# MainBoard.net
KiCad netlist of a schematic drawn in Altium Designer
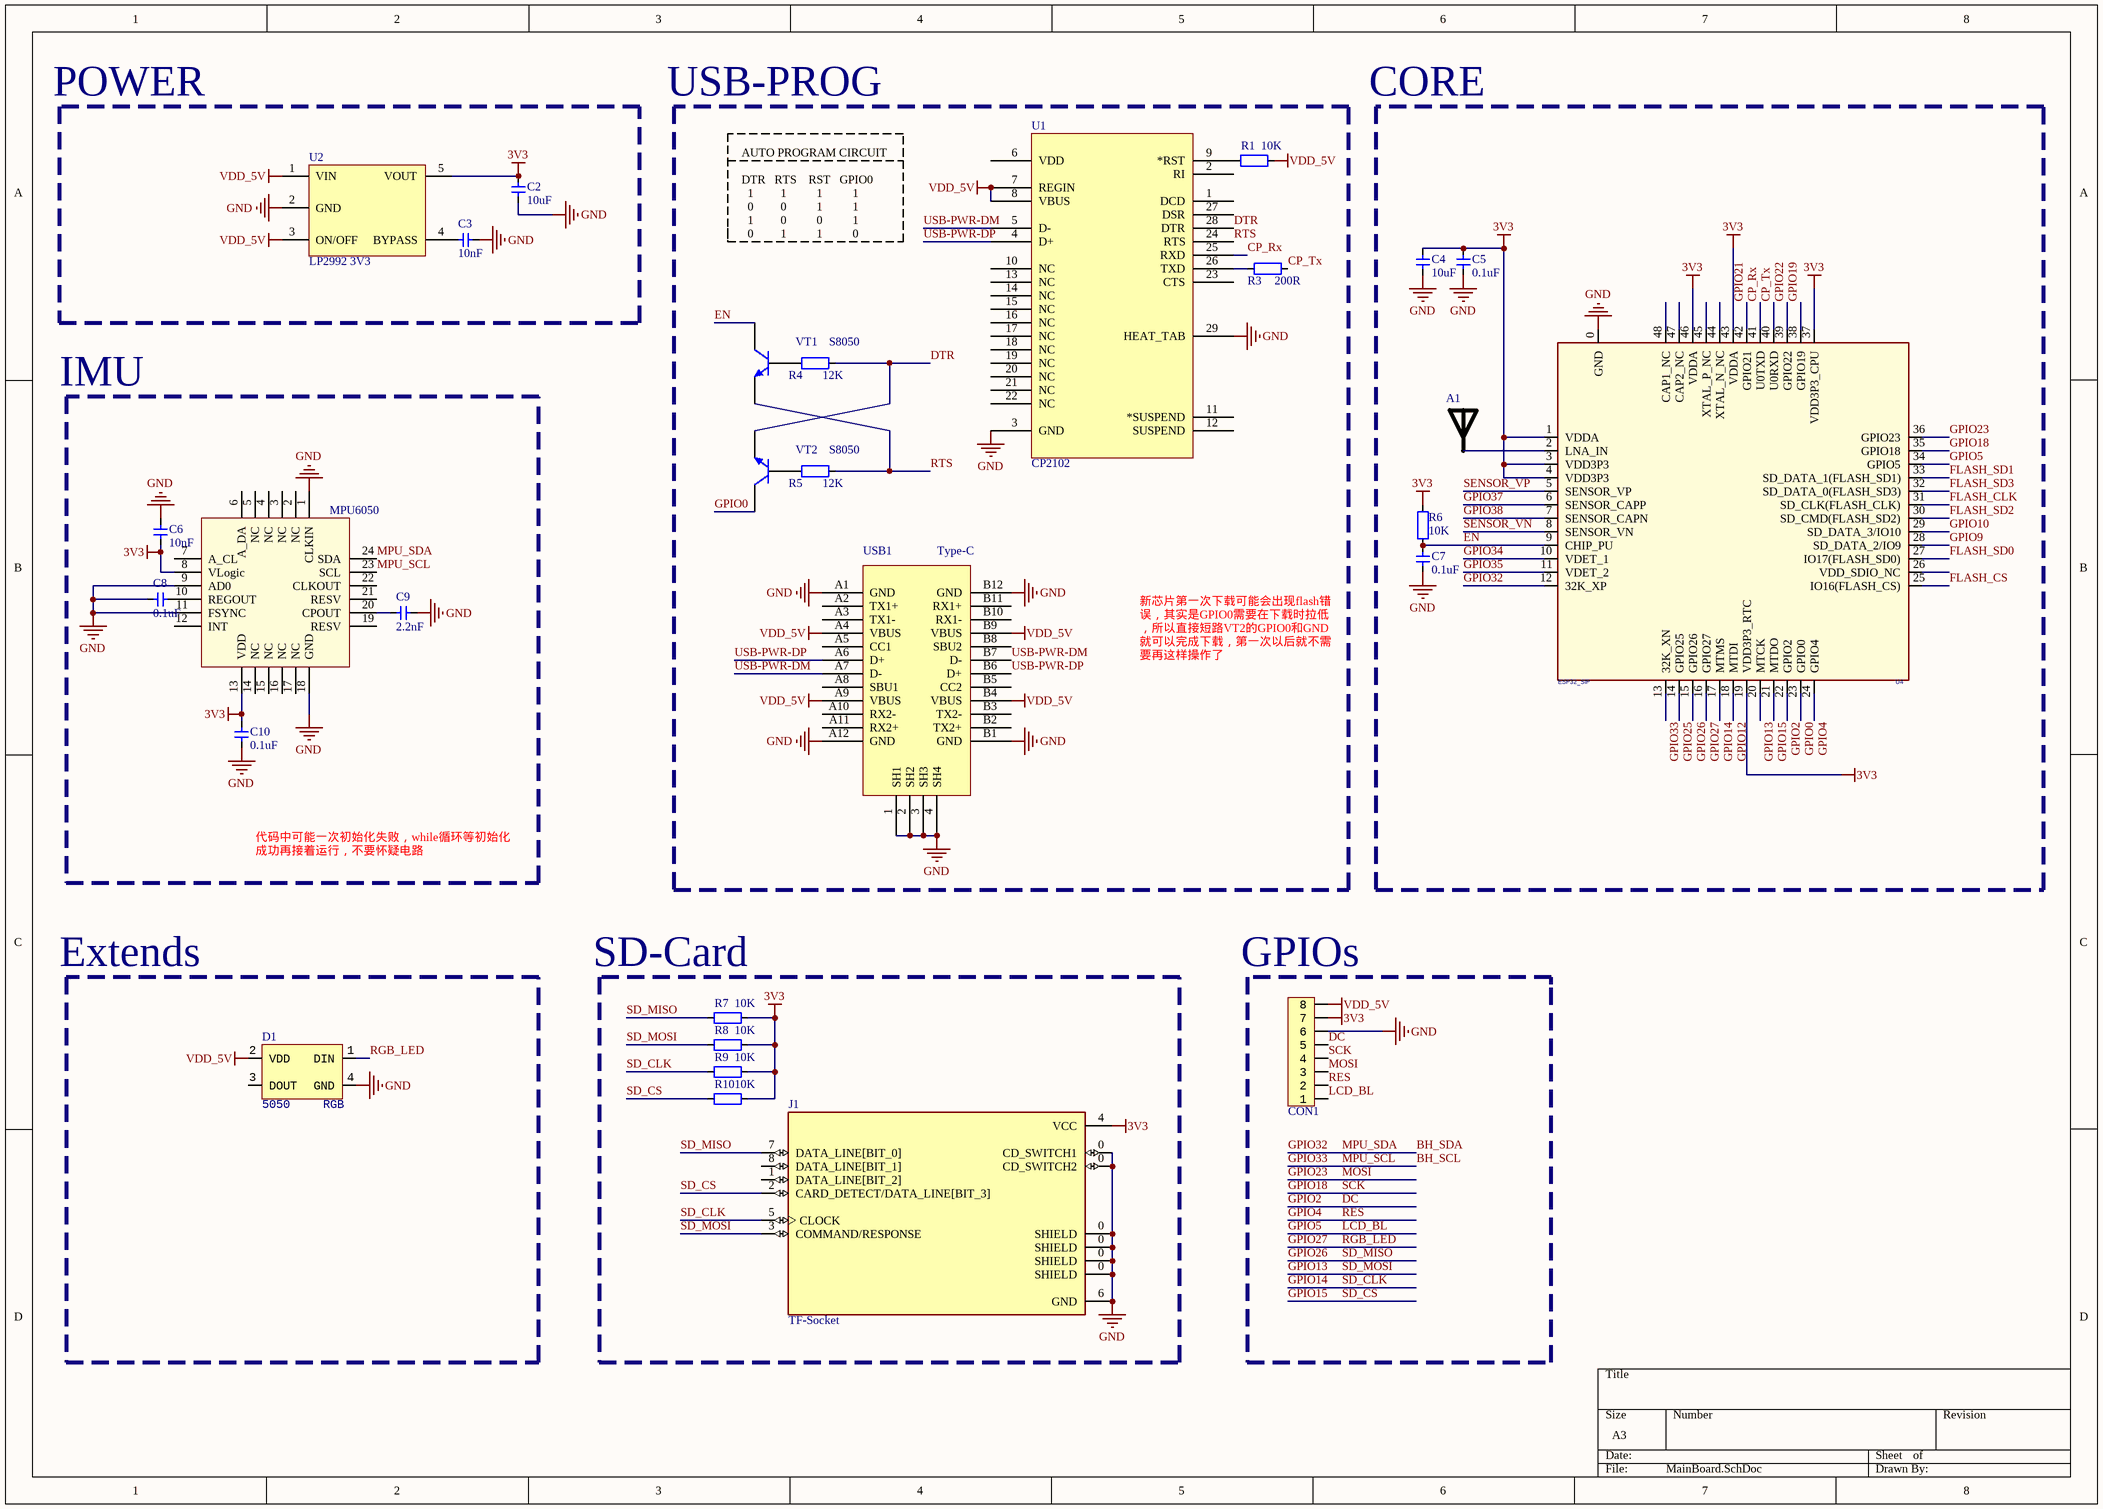
[diagram p0: MainBoard.SchDoc]

(export (version "E")
  (design (tool "Eeschema 10.0.6"))
  (components
    (comp (ref "A1")
      (value "RAINSUN")
      (footprint "ANT-Rainsun-AN5120")
      (libsource (lib "MyPcbLib") (part "ANT-Rainsun-AP5120"))
    )
    (comp (ref "C2")
      (value "10uF")
      (footprint "CAP_0402")
      (description "Capacitor")
      (libsource (lib "MyPcbLib") (part "电容-0402"))
    )
    (comp (ref "C3")
      (value "10nF")
      (footprint "CAP_0402")
      (description "Capacitor")
      (libsource (lib "MyPcbLib") (part "电容-0402"))
    )
    (comp (ref "C4")
      (value "10uF")
      (footprint "CAP_0402")
      (description "Capacitor")
      (libsource (lib "MyPcbLib") (part "电容-0402"))
    )
    (comp (ref "C5")
      (value "0.1uF")
      (footprint "CAP_0402")
      (description "Capacitor")
      (libsource (lib "MyPcbLib") (part "电容-0402"))
    )
    (comp (ref "C6")
      (value "10nF")
      (footprint "CAP_0402")
      (description "Capacitor")
      (libsource (lib "MyPcbLib") (part "电容-0402"))
    )
    (comp (ref "C7")
      (value "0.1uF")
      (footprint "CAP_0402")
      (description "Capacitor")
      (libsource (lib "MyPcbLib") (part "电容-0402"))
    )
    (comp (ref "C8")
      (value "0.1uF")
      (footprint "CAP_0402")
      (description "Capacitor")
      (libsource (lib "MyPcbLib") (part "电容-0402"))
    )
    (comp (ref "C9")
      (value "2.2nF")
      (footprint "CAP_0402")
      (description "Capacitor")
      (libsource (lib "MyPcbLib") (part "电容-0402"))
    )
    (comp (ref "C10")
      (value "0.1uF")
      (footprint "CAP_0402")
      (description "Capacitor")
      (libsource (lib "MyPcbLib") (part "电容-0402"))
    )
    (comp (ref "CON1")
      (value "FFC_0.5_8")
      (footprint "FFC_0.5_8")
      (description "FFC")
      (libsource (lib "KitSprout") (part "FFC_0.5_8"))
    )
    (comp (ref "D1")
      (value "RGB")
      (footprint "LED_WS2812_CE")
      (description "LED")
      (fields (field (name "TYPE") "5050"))
      (libsource (lib "KitSprout") (part "LED_5050_WS2812B"))
    )
    (comp (ref "J1")
      (value "TF-Socket")
      (footprint "TF_F")
      (description "10 _8 + 2_ Position Card Connector Secure Digital - microSDâ„¢ Surface Mount, Right Angle Gold")
      (fields (field (name "MP") "1140084168") (field (name "MF") "Amphenol Commercial Products"))
      (libsource (lib "MyPcbLib") (part "TF-Socket"))
    )
    (comp (ref "R1")
      (value "10K")
      (footprint "RES_0402")
      (description "Resistor")
      (libsource (lib "") (part "电阻-0402_1"))
    )
    (comp (ref "R3")
      (value "200R")
      (footprint "RES_0402")
      (description "Resistor")
      (libsource (lib "") (part "电阻-0402_1"))
    )
    (comp (ref "R4")
      (value "12K")
      (footprint "RES_0402")
      (description "Resistor")
      (libsource (lib "") (part "电阻-0402_1"))
    )
    (comp (ref "R5")
      (value "12K")
      (footprint "RES_0402")
      (description "Resistor")
      (libsource (lib "") (part "电阻-0402_1"))
    )
    (comp (ref "R6")
      (value "10K")
      (footprint "RES_0402")
      (description "Resistor")
      (libsource (lib "MyPcbLib") (part "电阻-0402"))
    )
    (comp (ref "R7")
      (value "10K")
      (footprint "RES_0402")
      (description "Resistor")
      (libsource (lib "") (part "电阻-0402_1"))
    )
    (comp (ref "R8")
      (value "10K")
      (footprint "RES_0402")
      (description "Resistor")
      (libsource (lib "") (part "电阻-0402_1"))
    )
    (comp (ref "R9")
      (value "10K")
      (footprint "RES_0402")
      (description "Resistor")
      (libsource (lib "") (part "电阻-0402_1"))
    )
    (comp (ref "R10")
      (value "10K")
      (footprint "RES_0402")
      (description "Resistor")
      (libsource (lib "") (part "电阻-0402_1"))
    )
    (comp (ref "U1")
      (value "CP2102")
      (footprint "QFN-28")
      (description "USB转TTL")
      (libsource (lib "mLib") (part "CP2102"))
    )
    (comp (ref "U2")
      (value "LP2992 3V3")
      (footprint "SOT23-5")
      (description "LDO")
      (libsource (lib "MyPcbLib") (part "LP2992"))
    )
    (comp (ref "U3")
      (value "MPU6050")
      (footprint "QFN-24")
      (description "六轴传感器")
      (libsource (lib "mLib") (part "MPU6050"))
    )
    (comp (ref "U4")
      (value "ESP32_SIP")
      (footprint "QFN-48_7X7")
      (libsource (lib "MyPcbLib") (part "ESP32-PICO"))
    )
    (comp (ref "USB1")
      (value "Type-C")
      (footprint "Type-C-TOP")
      (libsource (lib "MyPcbLib") (part "USB-Type-C-TOP"))
    )
    (comp (ref "VT1")
      (value "S8050")
      (footprint "SMT_TRIODE_NPN")
      (description "Surface mount NPN transistor, package SOT-23")
      (libsource (lib "MyPcbLib") (part "SMT_TRIODE_NPN"))
    )
    (comp (ref "VT2")
      (value "S8050")
      (footprint "SMT_TRIODE_NPN")
      (description "Surface mount NPN transistor, package SOT-23")
      (libsource (lib "MyPcbLib") (part "SMT_TRIODE_NPN"))
    )
  )
  (nets
    (net (code "1") (name "/BH_SCL") (class "Default")
      (node (ref "U3") (pin "23") (pinfunction "SCL_23") (pintype "passive"))
      (node (ref "U4") (pin "13") (pinfunction "32K_XN_13") (pintype "passive"))
    )
    (net (code "2") (name "/BH_SDA") (class "Default")
      (node (ref "U3") (pin "24") (pinfunction "SDA_24") (pintype "passive"))
      (node (ref "U4") (pin "12") (pinfunction "32K_XP_12") (pintype "passive"))
    )
    (net (code "3") (name "/CP_Rx") (class "Default")
      (node (ref "U1") (pin "25") (pinfunction "RXD_25") (pintype "passive"))
      (node (ref "U4") (pin "41") (pinfunction "U0TXD_41") (pintype "power_in"))
    )
    (net (code "4") (name "/CP_Tx") (class "Default")
      (node (ref "R3") (pin "1") (pinfunction "1_1") (pintype "passive"))
      (node (ref "U4") (pin "40") (pinfunction "U0RXD_40") (pintype "power_in"))
    )
    (net (code "5") (name "/DC") (class "Default")
      (node (ref "CON1") (pin "5") (pinfunction "5_5") (pintype "passive"))
      (node (ref "U4") (pin "22") (pinfunction "GPIO2_22") (pintype "passive"))
    )
    (net (code "6") (name "/DTR") (class "Default")
      (node (ref "R4") (pin "1") (pinfunction "1_1") (pintype "passive"))
      (node (ref "U1") (pin "28") (pinfunction "DTR_28") (pintype "passive"))
      (node (ref "VT2") (pin "2") (pinfunction "E_2") (pintype "passive"))
    )
    (net (code "7") (name "/EN") (class "Default")
      (node (ref "C7") (pin "1") (pinfunction "1_1") (pintype "passive"))
      (node (ref "R6") (pin "2") (pinfunction "2_2") (pintype "passive"))
      (node (ref "U4") (pin "9") (pinfunction "CHIP_PU_9") (pintype "passive"))
      (node (ref "VT1") (pin "3") (pinfunction "C_3") (pintype "passive"))
    )
    (net (code "8") (name "/FLASH_CLK") (class "Default")
      (node (ref "U4") (pin "31") (pinfunction "SD_CLK(FLASH_CLK)_31") (pintype "passive"))
    )
    (net (code "9") (name "/FLASH_CS") (class "Default")
      (node (ref "U4") (pin "25") (pinfunction "IO16(FLASH_CS)_25") (pintype "passive"))
    )
    (net (code "10") (name "/FLASH_SD0") (class "Default")
      (node (ref "U4") (pin "27") (pinfunction "IO17(FLASH_SD0)_27") (pintype "passive"))
    )
    (net (code "11") (name "/FLASH_SD1") (class "Default")
      (node (ref "U4") (pin "33") (pinfunction "SD_DATA_1(FLASH_SD1)_33") (pintype "passive"))
    )
    (net (code "12") (name "/FLASH_SD2") (class "Default")
      (node (ref "U4") (pin "30") (pinfunction "SD_CMD(FLASH_SD2)_30") (pintype "passive"))
    )
    (net (code "13") (name "/FLASH_SD3") (class "Default")
      (node (ref "U4") (pin "32") (pinfunction "SD_DATA_0(FLASH_SD3)_32") (pintype "passive"))
    )
    (net (code "14") (name "/GPIO0") (class "Default")
      (node (ref "U4") (pin "23") (pinfunction "GPIO0_23") (pintype "passive"))
      (node (ref "VT2") (pin "3") (pinfunction "C_3") (pintype "passive"))
    )
    (net (code "15") (name "/GPIO4") (class "Default")
      (node (ref "CON1") (pin "2") (pinfunction "2_2") (pintype "passive"))
      (node (ref "U4") (pin "24") (pinfunction "GPIO4_24") (pintype "passive"))
    )
    (net (code "16") (name "/GPIO5") (class "Default")
      (node (ref "CON1") (pin "1") (pinfunction "1_1") (pintype "passive"))
      (node (ref "U4") (pin "34") (pinfunction "GPIO5_34") (pintype "passive"))
    )
    (net (code "17") (name "/GPIO9") (class "Default")
      (node (ref "U4") (pin "28") (pinfunction "SD_DATA_2/IO9_28") (pintype "passive"))
    )
    (net (code "18") (name "/GPIO10") (class "Default")
      (node (ref "U4") (pin "29") (pinfunction "SD_DATA_3/IO10_29") (pintype "passive"))
    )
    (net (code "19") (name "/GPIO12") (class "Default")
      (node (ref "U4") (pin "18") (pinfunction "MTDI_18") (pintype "passive"))
    )
    (net (code "20") (name "/GPIO13") (class "Default")
      (node (ref "J1") (pin "3") (pinfunction "COMMAND/RESPONSE_3") (pintype "bidirectional"))
      (node (ref "R8") (pin "2") (pinfunction "2_2") (pintype "passive"))
      (node (ref "U4") (pin "20") (pinfunction "MTCK_20") (pintype "passive"))
    )
    (net (code "21") (name "/GPIO14") (class "Default")
      (node (ref "J1") (pin "5") (pinfunction "CLOCK_5") (pintype "bidirectional"))
      (node (ref "R9") (pin "2") (pinfunction "2_2") (pintype "passive"))
      (node (ref "U4") (pin "17") (pinfunction "MTMS_17") (pintype "passive"))
    )
    (net (code "22") (name "/GPIO15") (class "Default")
      (node (ref "J1") (pin "2") (pinfunction "CARD_DETECT/DATA_LINE[BIT_3]_2") (pintype "bidirectional"))
      (node (ref "R10") (pin "2") (pinfunction "2_2") (pintype "passive"))
      (node (ref "U4") (pin "21") (pinfunction "MTDO_21") (pintype "passive"))
    )
    (net (code "23") (name "/GPIO18") (class "Default")
      (node (ref "CON1") (pin "4") (pinfunction "4_4") (pintype "passive"))
      (node (ref "U4") (pin "35") (pinfunction "GPIO18_35") (pintype "passive"))
    )
    (net (code "24") (name "/GPIO19") (class "Default")
      (node (ref "U4") (pin "38") (pinfunction "GPIO19_38") (pintype "passive"))
    )
    (net (code "25") (name "/GPIO21") (class "Default")
      (node (ref "U4") (pin "42") (pinfunction "GPIO21_42") (pintype "passive"))
    )
    (net (code "26") (name "/GPIO22") (class "Default")
      (node (ref "U4") (pin "39") (pinfunction "GPIO22_39") (pintype "passive"))
    )
    (net (code "27") (name "/GPIO23") (class "Default")
      (node (ref "CON1") (pin "3") (pinfunction "3_3") (pintype "passive"))
      (node (ref "U4") (pin "36") (pinfunction "GPIO23_36") (pintype "passive"))
    )
    (net (code "28") (name "/GPIO25") (class "Default")
      (node (ref "U4") (pin "14") (pinfunction "GPIO25_14") (pintype "passive"))
    )
    (net (code "29") (name "/GPIO26") (class "Default")
      (node (ref "J1") (pin "7") (pinfunction "DATA_LINE[BIT_0]_7") (pintype "bidirectional"))
      (node (ref "R7") (pin "2") (pinfunction "2_2") (pintype "passive"))
      (node (ref "U4") (pin "15") (pinfunction "GPIO26_15") (pintype "passive"))
    )
    (net (code "30") (name "/GPIO27") (class "Default")
      (node (ref "D1") (pin "1") (pinfunction "DIN_1") (pintype "passive"))
      (node (ref "U4") (pin "16") (pinfunction "GPIO27_16") (pintype "passive"))
    )
    (net (code "31") (name "/GPIO34") (class "Default")
      (node (ref "U4") (pin "10") (pinfunction "VDET_1_10") (pintype "passive"))
    )
    (net (code "32") (name "/GPIO35") (class "Default")
      (node (ref "U4") (pin "11") (pinfunction "VDET_2_11") (pintype "passive"))
    )
    (net (code "33") (name "/GPIO37") (class "Default")
      (node (ref "U4") (pin "6") (pinfunction "SENSOR_CAPP_6") (pintype "passive"))
    )
    (net (code "34") (name "/GPIO38") (class "Default")
      (node (ref "U4") (pin "7") (pinfunction "SENSOR_CAPN_7") (pintype "passive"))
    )
    (net (code "35") (name "/RTS") (class "Default")
      (node (ref "R5") (pin "1") (pinfunction "1_1") (pintype "passive"))
      (node (ref "U1") (pin "24") (pinfunction "RTS_24") (pintype "passive"))
      (node (ref "VT1") (pin "2") (pinfunction "E_2") (pintype "passive"))
    )
    (net (code "36") (name "/SENSOR_VN") (class "Default")
      (node (ref "U4") (pin "8") (pinfunction "SENSOR_VN_8") (pintype "passive"))
    )
    (net (code "37") (name "/SENSOR_VP") (class "Default")
      (node (ref "U4") (pin "5") (pinfunction "SENSOR_VP_5") (pintype "passive"))
    )
    (net (code "38") (name "/USB-PWR-DM") (class "Default")
      (node (ref "U1") (pin "5") (pinfunction "D-_5") (pintype "passive"))
      (node (ref "USB1") (pin "A7") (pinfunction "D-_A7") (pintype "passive"))
      (node (ref "USB1") (pin "B7") (pinfunction "D-_B7") (pintype "passive"))
    )
    (net (code "39") (name "/USB-PWR-DP") (class "Default")
      (node (ref "U1") (pin "4") (pinfunction "D+_4") (pintype "passive"))
      (node (ref "USB1") (pin "A6") (pinfunction "D+_A6") (pintype "passive"))
      (node (ref "USB1") (pin "B6") (pinfunction "D+_B6") (pintype "passive"))
    )
    (net (code "40") (name "3V3") (class "Default")
      (node (ref "C10") (pin "2") (pinfunction "2_2") (pintype "passive"))
      (node (ref "C2") (pin "2") (pinfunction "2_2") (pintype "passive"))
      (node (ref "C4") (pin "2") (pinfunction "2_2") (pintype "passive"))
      (node (ref "C5") (pin "2") (pinfunction "2_2") (pintype "passive"))
      (node (ref "C6") (pin "1") (pinfunction "1_1") (pintype "passive"))
      (node (ref "CON1") (pin "7") (pinfunction "7_7") (pintype "passive"))
      (node (ref "J1") (pin "4") (pinfunction "VCC_4") (pintype "power_in"))
      (node (ref "R10") (pin "1") (pinfunction "1_1") (pintype "passive"))
      (node (ref "R6") (pin "1") (pinfunction "1_1") (pintype "passive"))
      (node (ref "R7") (pin "1") (pinfunction "1_1") (pintype "passive"))
      (node (ref "R8") (pin "1") (pinfunction "1_1") (pintype "passive"))
      (node (ref "R9") (pin "1") (pinfunction "1_1") (pintype "passive"))
      (node (ref "U2") (pin "5") (pinfunction "VOUT_5") (pintype "passive"))
      (node (ref "U3") (pin "13") (pinfunction "VDD_13") (pintype "passive"))
      (node (ref "U3") (pin "8") (pinfunction "VLogic_8") (pintype "passive"))
      (node (ref "U4") (pin "1") (pinfunction "VDDA_1") (pintype "power_in"))
      (node (ref "U4") (pin "19") (pinfunction "VDD3P3_RTC_19") (pintype "power_in"))
      (node (ref "U4") (pin "3") (pinfunction "VDD3P3_3") (pintype "power_in"))
      (node (ref "U4") (pin "37") (pinfunction "VDD3P3_CPU_37") (pintype "power_in"))
      (node (ref "U4") (pin "4") (pinfunction "VDD3P3_4") (pintype "power_in"))
      (node (ref "U4") (pin "43") (pinfunction "VDDA_43") (pintype "power_in"))
      (node (ref "U4") (pin "46") (pinfunction "VDDA_46") (pintype "power_in"))
    )
    (net (code "41") (name "GND") (class "Default")
      (node (ref "C10") (pin "1") (pinfunction "1_1") (pintype "passive"))
      (node (ref "C2") (pin "1") (pinfunction "1_1") (pintype "passive"))
      (node (ref "C3") (pin "1") (pinfunction "1_1") (pintype "passive"))
      (node (ref "C4") (pin "1") (pinfunction "1_1") (pintype "passive"))
      (node (ref "C5") (pin "1") (pinfunction "1_1") (pintype "passive"))
      (node (ref "C6") (pin "2") (pinfunction "2_2") (pintype "passive"))
      (node (ref "C7") (pin "2") (pinfunction "2_2") (pintype "passive"))
      (node (ref "C8") (pin "2") (pinfunction "2_2") (pintype "passive"))
      (node (ref "C9") (pin "1") (pinfunction "1_1") (pintype "passive"))
      (node (ref "CON1") (pin "6") (pinfunction "6_6") (pintype "passive"))
      (node (ref "D1") (pin "4") (pinfunction "GND_4") (pintype "passive"))
      (node (ref "J1") (pin "0") (pinfunction "SHIELD_0") (pintype "passive"))
      (node (ref "J1") (pin "6") (pinfunction "GND_6") (pintype "power_in"))
      (node (ref "U1") (pin "29") (pinfunction "HEAT_TAB_29") (pintype "passive"))
      (node (ref "U1") (pin "3") (pinfunction "GND_3") (pintype "passive"))
      (node (ref "U2") (pin "2") (pinfunction "GND_2") (pintype "passive"))
      (node (ref "U3") (pin "1") (pinfunction "CLKIN_1") (pintype "passive"))
      (node (ref "U3") (pin "11") (pinfunction "FSYNC_11") (pintype "passive"))
      (node (ref "U3") (pin "18") (pinfunction "GND_18") (pintype "passive"))
      (node (ref "U3") (pin "9") (pinfunction "AD0_9") (pintype "passive"))
      (node (ref "U4") (pin "0") (pinfunction "GND_0") (pintype "power_in"))
      (node (ref "USB1") (pin "1") (pinfunction "SH1_1") (pintype "passive"))
      (node (ref "USB1") (pin "2") (pinfunction "SH2_2") (pintype "passive"))
      (node (ref "USB1") (pin "3") (pinfunction "SH3_3") (pintype "passive"))
      (node (ref "USB1") (pin "4") (pinfunction "SH4_4") (pintype "passive"))
      (node (ref "USB1") (pin "A1") (pinfunction "GND_A1") (pintype "passive"))
      (node (ref "USB1") (pin "A12") (pinfunction "GND_A12") (pintype "passive"))
      (node (ref "USB1") (pin "B1") (pinfunction "GND_B1") (pintype "passive"))
      (node (ref "USB1") (pin "B12") (pinfunction "GND_B12") (pintype "passive"))
    )
    (net (code "42") (name "Net-(U1-*RST)") (class "Default")
      (node (ref "R1") (pin "2") (pinfunction "2_2") (pintype "passive"))
      (node (ref "U1") (pin "9") (pinfunction "*RST_9") (pintype "passive"))
    )
    (net (code "43") (name "Net-(U1-TXD)") (class "Default")
      (node (ref "R3") (pin "2") (pinfunction "2_2") (pintype "passive"))
      (node (ref "U1") (pin "26") (pinfunction "TXD_26") (pintype "passive"))
    )
    (net (code "44") (name "Net-(U2-BYPASS)") (class "Default")
      (node (ref "C3") (pin "2") (pinfunction "2_2") (pintype "passive"))
      (node (ref "U2") (pin "4") (pinfunction "BYPASS_4") (pintype "passive"))
    )
    (net (code "45") (name "Net-(U3-CPOUT)") (class "Default")
      (node (ref "C9") (pin "2") (pinfunction "2_2") (pintype "passive"))
      (node (ref "U3") (pin "20") (pinfunction "CPOUT_20") (pintype "passive"))
    )
    (net (code "46") (name "Net-(U3-REGOUT)") (class "Default")
      (node (ref "C8") (pin "1") (pinfunction "1_1") (pintype "passive"))
      (node (ref "U3") (pin "10") (pinfunction "REGOUT_10") (pintype "passive"))
    )
    (net (code "47") (name "Net-(U4-LNA_IN)") (class "Default")
      (node (ref "A1") (pin "1") (pinfunction "1_1") (pintype "passive"))
      (node (ref "U4") (pin "2") (pinfunction "LNA_IN_2") (pintype "passive"))
    )
    (net (code "48") (name "Net-(VT1-B)") (class "Default")
      (node (ref "R4") (pin "2") (pinfunction "2_2") (pintype "passive"))
      (node (ref "VT1") (pin "1") (pinfunction "B_1") (pintype "passive"))
    )
    (net (code "49") (name "Net-(VT2-B)") (class "Default")
      (node (ref "R5") (pin "2") (pinfunction "2_2") (pintype "passive"))
      (node (ref "VT2") (pin "1") (pinfunction "B_1") (pintype "passive"))
    )
    (net (code "50") (name "VDD_5V") (class "Default")
      (node (ref "CON1") (pin "8") (pinfunction "8_8") (pintype "passive"))
      (node (ref "D1") (pin "2") (pinfunction "VDD_2") (pintype "passive"))
      (node (ref "R1") (pin "1") (pinfunction "1_1") (pintype "passive"))
      (node (ref "U1") (pin "7") (pinfunction "REGIN_7") (pintype "passive"))
      (node (ref "U1") (pin "8") (pinfunction "VBUS_8") (pintype "passive"))
      (node (ref "U2") (pin "1") (pinfunction "VIN_1") (pintype "passive"))
      (node (ref "U2") (pin "3") (pinfunction "ON/OFF_3") (pintype "passive"))
      (node (ref "USB1") (pin "A4") (pinfunction "VBUS_A4") (pintype "passive"))
      (node (ref "USB1") (pin "A9") (pinfunction "VBUS_A9") (pintype "passive"))
      (node (ref "USB1") (pin "B4") (pinfunction "VBUS_B4") (pintype "passive"))
      (node (ref "USB1") (pin "B9") (pinfunction "VBUS_B9") (pintype "passive"))
    )
    (net (code "51") (name "unconnected-(D1-DOUT-Pad3)") (class "Default")
      (node (ref "D1") (pin "3") (pinfunction "DOUT_3") (pintype "passive"))
    )
    (net (code "52") (name "unconnected-(J1-DATA_LINE[BIT_1]-Pad8)") (class "Default")
      (node (ref "J1") (pin "8") (pinfunction "DATA_LINE[BIT_1]_8") (pintype "bidirectional"))
    )
    (net (code "53") (name "unconnected-(J1-DATA_LINE[BIT_2]-Pad1)") (class "Default")
      (node (ref "J1") (pin "1") (pinfunction "DATA_LINE[BIT_2]_1") (pintype "bidirectional"))
    )
    (net (code "54") (name "unconnected-(U1-*SUSPEND-Pad11)") (class "Default")
      (node (ref "U1") (pin "11") (pinfunction "*SUSPEND_11") (pintype "passive"))
    )
    (net (code "55") (name "unconnected-(U1-CTS-Pad23)") (class "Default")
      (node (ref "U1") (pin "23") (pinfunction "CTS_23") (pintype "passive"))
    )
    (net (code "56") (name "unconnected-(U1-DCD-Pad1)") (class "Default")
      (node (ref "U1") (pin "1") (pinfunction "DCD_1") (pintype "passive"))
    )
    (net (code "57") (name "unconnected-(U1-DSR-Pad27)") (class "Default")
      (node (ref "U1") (pin "27") (pinfunction "DSR_27") (pintype "passive"))
    )
    (net (code "58") (name "unconnected-(U1-NC-Pad10)") (class "Default")
      (node (ref "U1") (pin "10") (pinfunction "NC_10") (pintype "passive"))
    )
    (net (code "59") (name "unconnected-(U1-NC-Pad13)") (class "Default")
      (node (ref "U1") (pin "13") (pinfunction "NC_13") (pintype "passive"))
    )
    (net (code "60") (name "unconnected-(U1-NC-Pad14)") (class "Default")
      (node (ref "U1") (pin "14") (pinfunction "NC_14") (pintype "passive"))
    )
    (net (code "61") (name "unconnected-(U1-NC-Pad15)") (class "Default")
      (node (ref "U1") (pin "15") (pinfunction "NC_15") (pintype "passive"))
    )
    (net (code "62") (name "unconnected-(U1-NC-Pad16)") (class "Default")
      (node (ref "U1") (pin "16") (pinfunction "NC_16") (pintype "passive"))
    )
    (net (code "63") (name "unconnected-(U1-NC-Pad17)") (class "Default")
      (node (ref "U1") (pin "17") (pinfunction "NC_17") (pintype "passive"))
    )
    (net (code "64") (name "unconnected-(U1-NC-Pad18)") (class "Default")
      (node (ref "U1") (pin "18") (pinfunction "NC_18") (pintype "passive"))
    )
    (net (code "65") (name "unconnected-(U1-NC-Pad19)") (class "Default")
      (node (ref "U1") (pin "19") (pinfunction "NC_19") (pintype "passive"))
    )
    (net (code "66") (name "unconnected-(U1-NC-Pad20)") (class "Default")
      (node (ref "U1") (pin "20") (pinfunction "NC_20") (pintype "passive"))
    )
    (net (code "67") (name "unconnected-(U1-NC-Pad21)") (class "Default")
      (node (ref "U1") (pin "21") (pinfunction "NC_21") (pintype "passive"))
    )
    (net (code "68") (name "unconnected-(U1-NC-Pad22)") (class "Default")
      (node (ref "U1") (pin "22") (pinfunction "NC_22") (pintype "passive"))
    )
    (net (code "69") (name "unconnected-(U1-RI-Pad2)") (class "Default")
      (node (ref "U1") (pin "2") (pinfunction "RI_2") (pintype "passive"))
    )
    (net (code "70") (name "unconnected-(U1-SUSPEND-Pad12)") (class "Default")
      (node (ref "U1") (pin "12") (pinfunction "SUSPEND_12") (pintype "passive"))
    )
    (net (code "71") (name "unconnected-(U1-VDD-Pad6)") (class "Default")
      (node (ref "U1") (pin "6") (pinfunction "VDD_6") (pintype "passive"))
    )
    (net (code "72") (name "unconnected-(U3-A_CL-Pad7)") (class "Default")
      (node (ref "U3") (pin "7") (pinfunction "A_CL_7") (pintype "passive"))
    )
    (net (code "73") (name "unconnected-(U3-A_DA-Pad6)") (class "Default")
      (node (ref "U3") (pin "6") (pinfunction "A_DA_6") (pintype "passive"))
    )
    (net (code "74") (name "unconnected-(U3-CLKOUT-Pad22)") (class "Default")
      (node (ref "U3") (pin "22") (pinfunction "CLKOUT_22") (pintype "passive"))
    )
    (net (code "75") (name "unconnected-(U3-INT-Pad12)") (class "Default")
      (node (ref "U3") (pin "12") (pinfunction "INT_12") (pintype "passive"))
    )
    (net (code "76") (name "unconnected-(U3-NC-Pad2)") (class "Default")
      (node (ref "U3") (pin "2") (pinfunction "NC_2") (pintype "passive"))
    )
    (net (code "77") (name "unconnected-(U3-NC-Pad3)") (class "Default")
      (node (ref "U3") (pin "3") (pinfunction "NC_3") (pintype "passive"))
    )
    (net (code "78") (name "unconnected-(U3-NC-Pad4)") (class "Default")
      (node (ref "U3") (pin "4") (pinfunction "NC_4") (pintype "passive"))
    )
    (net (code "79") (name "unconnected-(U3-NC-Pad5)") (class "Default")
      (node (ref "U3") (pin "5") (pinfunction "NC_5") (pintype "passive"))
    )
    (net (code "80") (name "unconnected-(U3-NC-Pad14)") (class "Default")
      (node (ref "U3") (pin "14") (pinfunction "NC_14") (pintype "passive"))
    )
    (net (code "81") (name "unconnected-(U3-NC-Pad15)") (class "Default")
      (node (ref "U3") (pin "15") (pinfunction "NC_15") (pintype "passive"))
    )
    (net (code "82") (name "unconnected-(U3-NC-Pad16)") (class "Default")
      (node (ref "U3") (pin "16") (pinfunction "NC_16") (pintype "passive"))
    )
    (net (code "83") (name "unconnected-(U3-NC-Pad17)") (class "Default")
      (node (ref "U3") (pin "17") (pinfunction "NC_17") (pintype "passive"))
    )
    (net (code "84") (name "unconnected-(U3-RESV-Pad19)") (class "Default")
      (node (ref "U3") (pin "19") (pinfunction "RESV_19") (pintype "passive"))
    )
    (net (code "85") (name "unconnected-(U3-RESV-Pad21)") (class "Default")
      (node (ref "U3") (pin "21") (pinfunction "RESV_21") (pintype "passive"))
    )
    (net (code "86") (name "unconnected-(U4-CAP1_NC-Pad48)") (class "Default")
      (node (ref "U4") (pin "48") (pinfunction "CAP1_NC_48") (pintype "passive"))
    )
    (net (code "87") (name "unconnected-(U4-CAP2_NC-Pad47)") (class "Default")
      (node (ref "U4") (pin "47") (pinfunction "CAP2_NC_47") (pintype "passive"))
    )
    (net (code "88") (name "unconnected-(U4-VDD_SDIO_NC-Pad26)") (class "Default")
      (node (ref "U4") (pin "26") (pinfunction "VDD_SDIO_NC_26") (pintype "passive"))
    )
    (net (code "89") (name "unconnected-(U4-XTAL_N_NC-Pad44)") (class "Default")
      (node (ref "U4") (pin "44") (pinfunction "XTAL_N_NC_44") (pintype "passive"))
    )
    (net (code "90") (name "unconnected-(U4-XTAL_P_NC-Pad45)") (class "Default")
      (node (ref "U4") (pin "45") (pinfunction "XTAL_P_NC_45") (pintype "passive"))
    )
    (net (code "91") (name "unconnected-(USB1-CC1-PadA5)") (class "Default")
      (node (ref "USB1") (pin "A5") (pinfunction "CC1_A5") (pintype "passive"))
    )
    (net (code "92") (name "unconnected-(USB1-CC2-PadB5)") (class "Default")
      (node (ref "USB1") (pin "B5") (pinfunction "CC2_B5") (pintype "passive"))
    )
    (net (code "93") (name "unconnected-(USB1-RX1+-PadB11)") (class "Default")
      (node (ref "USB1") (pin "B11") (pinfunction "RX1+_B11") (pintype "passive"))
    )
    (net (code "94") (name "unconnected-(USB1-RX1--PadB10)") (class "Default")
      (node (ref "USB1") (pin "B10") (pinfunction "RX1-_B10") (pintype "passive"))
    )
    (net (code "95") (name "unconnected-(USB1-RX2+-PadA11)") (class "Default")
      (node (ref "USB1") (pin "A11") (pinfunction "RX2+_A11") (pintype "passive"))
    )
    (net (code "96") (name "unconnected-(USB1-RX2--PadA10)") (class "Default")
      (node (ref "USB1") (pin "A10") (pinfunction "RX2-_A10") (pintype "passive"))
    )
    (net (code "97") (name "unconnected-(USB1-SBU1-PadA8)") (class "Default")
      (node (ref "USB1") (pin "A8") (pinfunction "SBU1_A8") (pintype "passive"))
    )
    (net (code "98") (name "unconnected-(USB1-SBU2-PadB8)") (class "Default")
      (node (ref "USB1") (pin "B8") (pinfunction "SBU2_B8") (pintype "passive"))
    )
    (net (code "99") (name "unconnected-(USB1-TX1+-PadA2)") (class "Default")
      (node (ref "USB1") (pin "A2") (pinfunction "TX1+_A2") (pintype "passive"))
    )
    (net (code "100") (name "unconnected-(USB1-TX1--PadA3)") (class "Default")
      (node (ref "USB1") (pin "A3") (pinfunction "TX1-_A3") (pintype "passive"))
    )
    (net (code "101") (name "unconnected-(USB1-TX2+-PadB2)") (class "Default")
      (node (ref "USB1") (pin "B2") (pinfunction "TX2+_B2") (pintype "passive"))
    )
    (net (code "102") (name "unconnected-(USB1-TX2--PadB3)") (class "Default")
      (node (ref "USB1") (pin "B3") (pinfunction "TX2-_B3") (pintype "passive"))
    )
  )
)
